# Connectors.net
KiCad netlist of a schematic drawn in Altium Designer
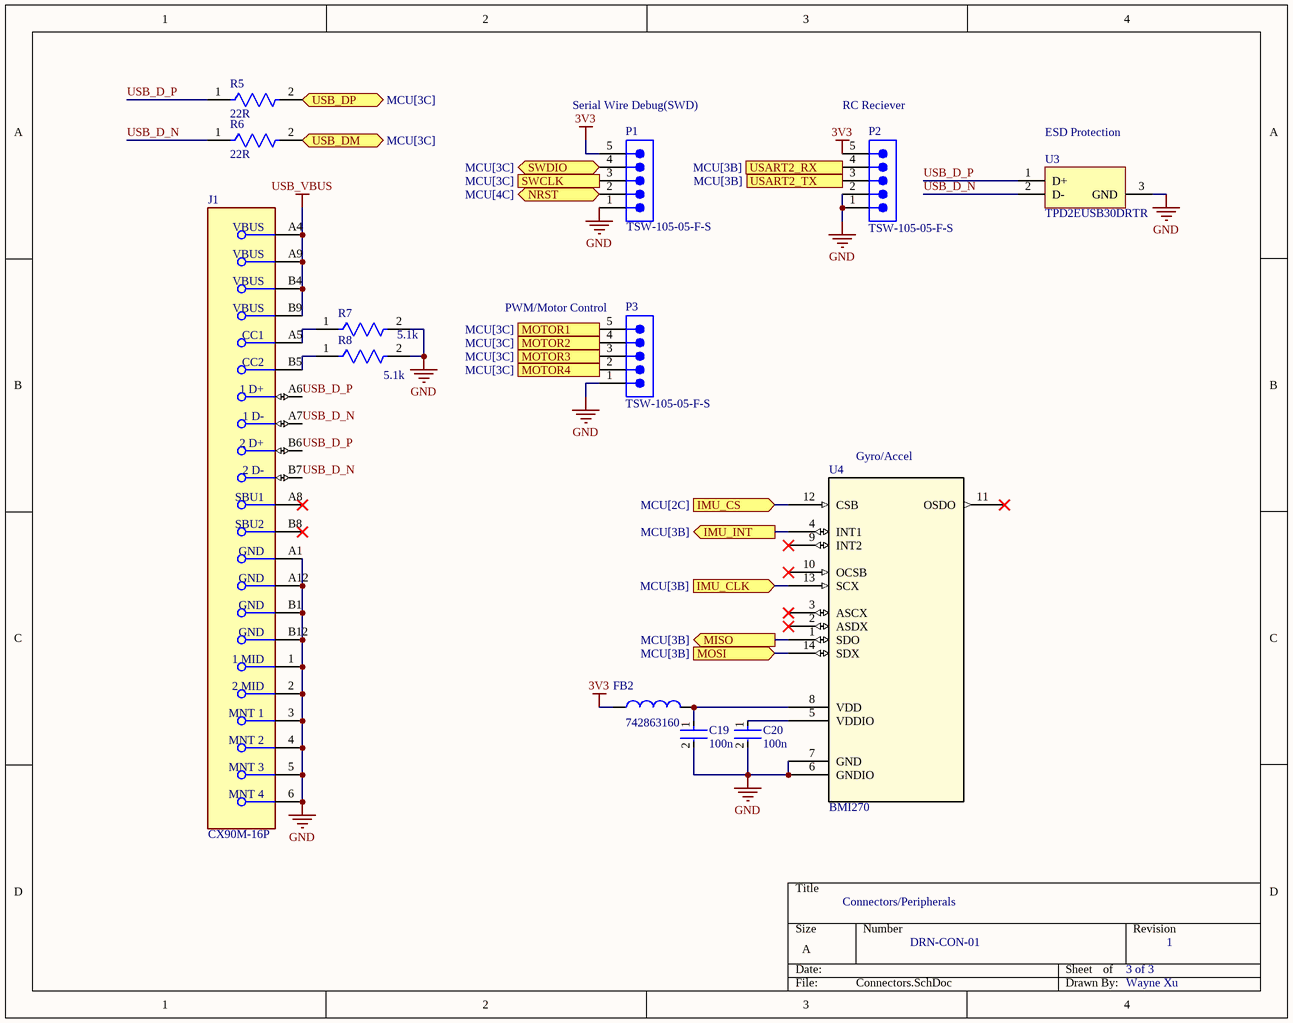
[diagram p0: Connectors.SchDoc]

(export (version "E")
  (design (tool "Eeschema 10.0.6"))
  (components
    (comp (ref "C19")
      (value "100n")
      (footprint "FP-C0603C-CF-MFG")
      (description "CAP CER 0.1UF 25V Y5V 0603")
      (fields (field (name "MANUFACTURER PART NUMBER") "C0603C104M3VACTU") (field (name "TOLERANCE") "0.2"))
      (libsource (lib "Altium Content Vault") (part "b4654b650e69147ec39a6b967a45e02"))
    )
    (comp (ref "C20")
      (value "100n")
      (footprint "FP-C0603C-CF-MFG")
      (description "CAP CER 0.1UF 25V Y5V 0603")
      (fields (field (name "MANUFACTURER PART NUMBER") "C0603C104M3VACTU") (field (name "TOLERANCE") "0.2"))
      (libsource (lib "Altium Content Vault") (part "b4654b650e69147ec39a6b967a45e02"))
    )
    (comp (ref "FB2")
      (value "742863160")
      (footprint "WE-CBF HF_0603_HC")
      (description "Ferrite Bead (emi Suppression), 1.6X0.8X0.8MM (0603), 600O Impedance At 100 Mhz")
      (fields (field (name "TOLERANCE") "25%"))
      (libsource (lib "Altium Content Vault") (part "Ferrite"))
    )
    (comp (ref "J1")
      (value "CX90M-16P")
      (footprint "FP-CX90M-16P-MFG")
      (description "CONN RCPT USB2.0 TYPEC 16POS SMD")
      (libsource (lib "Altium Content Vault") (part "6b7e9819a715c2d1d3babe584a73dea"))
    )
    (comp (ref "P1")
      (value "TSW-105-05-F-S")
      (footprint "SMTC-TSW-105-05-X-S")
      (description "0.025\" SQ Post Header, Through-hole, Vertical, -55 to 125 degC, 2.54 mm Pitch, 5-Pin, Male, RoHS")
      (fields (field (name "MANUFACTURER") "Samtec"))
      (libsource (lib "Altium Content Vault") (part "SMTC-TSW-105-05-X-S"))
    )
    (comp (ref "P2")
      (value "TSW-105-05-F-S")
      (footprint "SMTC-TSW-105-05-X-S")
      (description "0.025\" SQ Post Header, Through-hole, Vertical, -55 to 125 degC, 2.54 mm Pitch, 5-Pin, Male, RoHS")
      (fields (field (name "MANUFACTURER") "Samtec"))
      (libsource (lib "Altium Content Vault") (part "SMTC-TSW-105-05-X-S"))
    )
    (comp (ref "P3")
      (value "TSW-105-05-F-S")
      (footprint "SMTC-TSW-105-05-X-S")
      (description "0.025\" SQ Post Header, Through-hole, Vertical, -55 to 125 degC, 2.54 mm Pitch, 5-Pin, Male, RoHS")
      (fields (field (name "MANUFACTURER") "Samtec"))
      (libsource (lib "Altium Content Vault") (part "SMTC-TSW-105-05-X-S"))
    )
    (comp (ref "R5")
      (value "22R")
      (footprint "FP-CRGCQ0603-IPC_C")
      (description "CRGCQ 0603 22R 1%")
      (fields
        (field (name "OCTOPART") "https://octopart.com/crgcq0603f22r-te+connectivity-91018058")
        (field (name "MANUFACTURER") "TE Connectivity")
      )
      (libsource (lib "Altium Content Vault") (part "1029c3af85768c4190bb7ad29bc67b5"))
    )
    (comp (ref "R6")
      (value "22R")
      (footprint "FP-CRGCQ0603-IPC_C")
      (description "CRGCQ 0603 22R 1%")
      (fields
        (field (name "OCTOPART") "https://octopart.com/crgcq0603f22r-te+connectivity-91018058")
        (field (name "MANUFACTURER") "TE Connectivity")
      )
      (libsource (lib "Altium Content Vault") (part "1029c3af85768c4190bb7ad29bc67b5"))
    )
    (comp (ref "R7")
      (value "5.1k")
      (footprint "FP-RN73R1E-IPC_C")
      (description "5.1kΩ ±1% 0.063W, 1/16W Chip Resistor 0402 (1005 Metric) Moisture Resistant Thin Film")
      (libsource (lib "Altium Content Vault") (part "1029c3af85768c4190bb7ad29bc67b5"))
    )
    (comp (ref "R8")
      (value "5.1k")
      (footprint "FP-RN73R1E-IPC_C")
      (description "5.1kΩ ±1% 0.063W, 1/16W Chip Resistor 0402 (1005 Metric) Moisture Resistant Thin Film")
      (libsource (lib "Altium Content Vault") (part "1029c3af85768c4190bb7ad29bc67b5"))
    )
    (comp (ref "U3")
      (value "TPD2EUSB30DRTR")
      (footprint "DRT0003A")
      (fields (field (name "MANUFACTURER") "Texas Instruments"))
      (libsource (lib "Altium Content Vault") (part "TI-TPD2EUSB30-SOT_DRT-3"))
    )
    (comp (ref "U4")
      (value "BMI270")
      (footprint "BMI270:BMI270_BOS")
      (description "Description")
      (fields (field (name "COPYRIGHT") "Copyright (C) 2025 Ultra Librarian. All rights reserved."))
      (libsource (lib "BMI270") (part "BMI270"))
    )
  )
  (nets
    (net (code "1") (name "/IMU_CLK") (class "Default")
      (node (ref "U4") (pin "13") (pinfunction "SCX_13") (pintype "input"))
    )
    (net (code "2") (name "/IMU_CS") (class "Default")
      (node (ref "U4") (pin "12") (pinfunction "CSB_12") (pintype "input"))
    )
    (net (code "3") (name "/IMU_INT") (class "Default")
      (node (ref "U4") (pin "4") (pinfunction "INT1_4") (pintype "bidirectional"))
    )
    (net (code "4") (name "/MISO") (class "Default")
      (node (ref "U4") (pin "1") (pinfunction "SDO_1") (pintype "bidirectional"))
    )
    (net (code "5") (name "/MOSI") (class "Default")
      (node (ref "U4") (pin "14") (pinfunction "SDX_14") (pintype "bidirectional"))
    )
    (net (code "6") (name "/MOTOR1") (class "Default")
      (node (ref "P3") (pin "5") (pinfunction "5_5") (pintype "passive"))
    )
    (net (code "7") (name "/MOTOR2") (class "Default")
      (node (ref "P3") (pin "4") (pinfunction "4_4") (pintype "passive"))
    )
    (net (code "8") (name "/MOTOR3") (class "Default")
      (node (ref "P3") (pin "3") (pinfunction "3_3") (pintype "passive"))
    )
    (net (code "9") (name "/MOTOR4") (class "Default")
      (node (ref "P3") (pin "2") (pinfunction "2_2") (pintype "passive"))
    )
    (net (code "10") (name "/NRST") (class "Default")
      (node (ref "P1") (pin "2") (pinfunction "2_2") (pintype "passive"))
    )
    (net (code "11") (name "/SWCLK") (class "Default")
      (node (ref "P1") (pin "3") (pinfunction "3_3") (pintype "passive"))
    )
    (net (code "12") (name "/SWDIO") (class "Default")
      (node (ref "P1") (pin "4") (pinfunction "4_4") (pintype "passive"))
    )
    (net (code "13") (name "/USART2_RX") (class "Default")
      (node (ref "P2") (pin "4") (pinfunction "4_4") (pintype "passive"))
    )
    (net (code "14") (name "/USART2_TX") (class "Default")
      (node (ref "P2") (pin "3") (pinfunction "3_3") (pintype "passive"))
    )
    (net (code "15") (name "/USB_DM") (class "Default")
      (node (ref "R6") (pin "2") (pinfunction "2_2") (pintype "passive"))
    )
    (net (code "16") (name "/USB_DP") (class "Default")
      (node (ref "R5") (pin "2") (pinfunction "2_2") (pintype "passive"))
    )
    (net (code "17") (name "/USB_D_N") (class "Default")
      (node (ref "J1") (pin "A7") (pinfunction "1_D-_A7") (pintype "bidirectional"))
      (node (ref "J1") (pin "B7") (pinfunction "2_D-_B7") (pintype "bidirectional"))
      (node (ref "R6") (pin "1") (pinfunction "1_1") (pintype "passive"))
      (node (ref "U3") (pin "2") (pinfunction "D-_2") (pintype "passive"))
    )
    (net (code "18") (name "/USB_D_P") (class "Default")
      (node (ref "J1") (pin "A6") (pinfunction "1_D+_A6") (pintype "bidirectional"))
      (node (ref "J1") (pin "B6") (pinfunction "2_D+_B6") (pintype "bidirectional"))
      (node (ref "R5") (pin "1") (pinfunction "1_1") (pintype "passive"))
      (node (ref "U3") (pin "1") (pinfunction "D+_1") (pintype "passive"))
    )
    (net (code "19") (name "3V3") (class "Default")
      (node (ref "FB2") (pin "1") (pinfunction "1_1") (pintype "passive"))
      (node (ref "P1") (pin "5") (pinfunction "5_5") (pintype "passive"))
      (node (ref "P2") (pin "5") (pinfunction "5_5") (pintype "passive"))
    )
    (net (code "20") (name "GND") (class "Default")
      (node (ref "C19") (pin "2") (pinfunction "2_2") (pintype "passive"))
      (node (ref "C20") (pin "2") (pinfunction "2_2") (pintype "passive"))
      (node (ref "J1") (pin "1") (pinfunction "1_MID_1") (pintype "passive"))
      (node (ref "J1") (pin "2") (pinfunction "2_MID_2") (pintype "passive"))
      (node (ref "J1") (pin "3") (pinfunction "MNT_1_3") (pintype "passive"))
      (node (ref "J1") (pin "4") (pinfunction "MNT_2_4") (pintype "passive"))
      (node (ref "J1") (pin "5") (pinfunction "MNT_3_5") (pintype "passive"))
      (node (ref "J1") (pin "6") (pinfunction "MNT_4_6") (pintype "passive"))
      (node (ref "J1") (pin "A1") (pinfunction "GND_A1") (pintype "power_in"))
      (node (ref "J1") (pin "A12") (pinfunction "GND_A12") (pintype "power_in"))
      (node (ref "J1") (pin "B1") (pinfunction "GND_B1") (pintype "power_in"))
      (node (ref "J1") (pin "B12") (pinfunction "GND_B12") (pintype "power_in"))
      (node (ref "P1") (pin "1") (pinfunction "1_1") (pintype "passive"))
      (node (ref "P2") (pin "1") (pinfunction "1_1") (pintype "passive"))
      (node (ref "P2") (pin "2") (pinfunction "2_2") (pintype "passive"))
      (node (ref "P3") (pin "1") (pinfunction "1_1") (pintype "passive"))
      (node (ref "R7") (pin "2") (pinfunction "2_2") (pintype "passive"))
      (node (ref "R8") (pin "2") (pinfunction "2_2") (pintype "passive"))
      (node (ref "U3") (pin "3") (pinfunction "GND_3") (pintype "power_in"))
      (node (ref "U4") (pin "6") (pinfunction "GNDIO_6") (pintype "power_in"))
      (node (ref "U4") (pin "7") (pinfunction "GND_7") (pintype "power_in"))
    )
    (net (code "21") (name "Net-(J1-CC1)") (class "Default")
      (node (ref "J1") (pin "A5") (pinfunction "CC1_A5") (pintype "passive"))
      (node (ref "R7") (pin "1") (pinfunction "1_1") (pintype "passive"))
    )
    (net (code "22") (name "Net-(J1-CC2)") (class "Default")
      (node (ref "J1") (pin "B5") (pinfunction "CC2_B5") (pintype "passive"))
      (node (ref "R8") (pin "1") (pinfunction "1_1") (pintype "passive"))
    )
    (net (code "23") (name "Net-(U4-VDD)") (class "Default")
      (node (ref "C19") (pin "1") (pinfunction "1_1") (pintype "passive"))
      (node (ref "FB2") (pin "2") (pinfunction "2_2") (pintype "passive"))
      (node (ref "U4") (pin "8") (pinfunction "VDD_8") (pintype "power_in"))
    )
    (net (code "24") (name "Net-(U4-VDDIO)") (class "Default")
      (node (ref "C20") (pin "1") (pinfunction "1_1") (pintype "passive"))
      (node (ref "U4") (pin "5") (pinfunction "VDDIO_5") (pintype "power_in"))
    )
    (net (code "25") (name "USB_VBUS") (class "Default")
      (node (ref "J1") (pin "A4") (pinfunction "VBUS_A4") (pintype "power_in"))
      (node (ref "J1") (pin "A9") (pinfunction "VBUS_A9") (pintype "power_in"))
      (node (ref "J1") (pin "B4") (pinfunction "VBUS_B4") (pintype "power_in"))
      (node (ref "J1") (pin "B9") (pinfunction "VBUS_B9") (pintype "power_in"))
    )
    (net (code "26") (name "unconnected-(J1-SBU1-PadA8)") (class "Default")
      (node (ref "J1") (pin "A8") (pinfunction "SBU1_A8") (pintype "passive+no_connect"))
    )
    (net (code "27") (name "unconnected-(J1-SBU2-PadB8)") (class "Default")
      (node (ref "J1") (pin "B8") (pinfunction "SBU2_B8") (pintype "passive+no_connect"))
    )
    (net (code "28") (name "unconnected-(U4-ASCX-Pad3)") (class "Default")
      (node (ref "U4") (pin "3") (pinfunction "ASCX_3") (pintype "bidirectional+no_connect"))
    )
    (net (code "29") (name "unconnected-(U4-ASDX-Pad2)") (class "Default")
      (node (ref "U4") (pin "2") (pinfunction "ASDX_2") (pintype "bidirectional+no_connect"))
    )
    (net (code "30") (name "unconnected-(U4-INT2-Pad9)") (class "Default")
      (node (ref "U4") (pin "9") (pinfunction "INT2_9") (pintype "bidirectional+no_connect"))
    )
    (net (code "31") (name "unconnected-(U4-OCSB-Pad10)") (class "Default")
      (node (ref "U4") (pin "10") (pinfunction "OCSB_10") (pintype "input+no_connect"))
    )
    (net (code "32") (name "unconnected-(U4-OSDO-Pad11)") (class "Default")
      (node (ref "U4") (pin "11") (pinfunction "OSDO_11") (pintype "output+no_connect"))
    )
  )
)
